# asam_mit_RFM.net
KiCad netlist of a schematic drawn in EAGLE
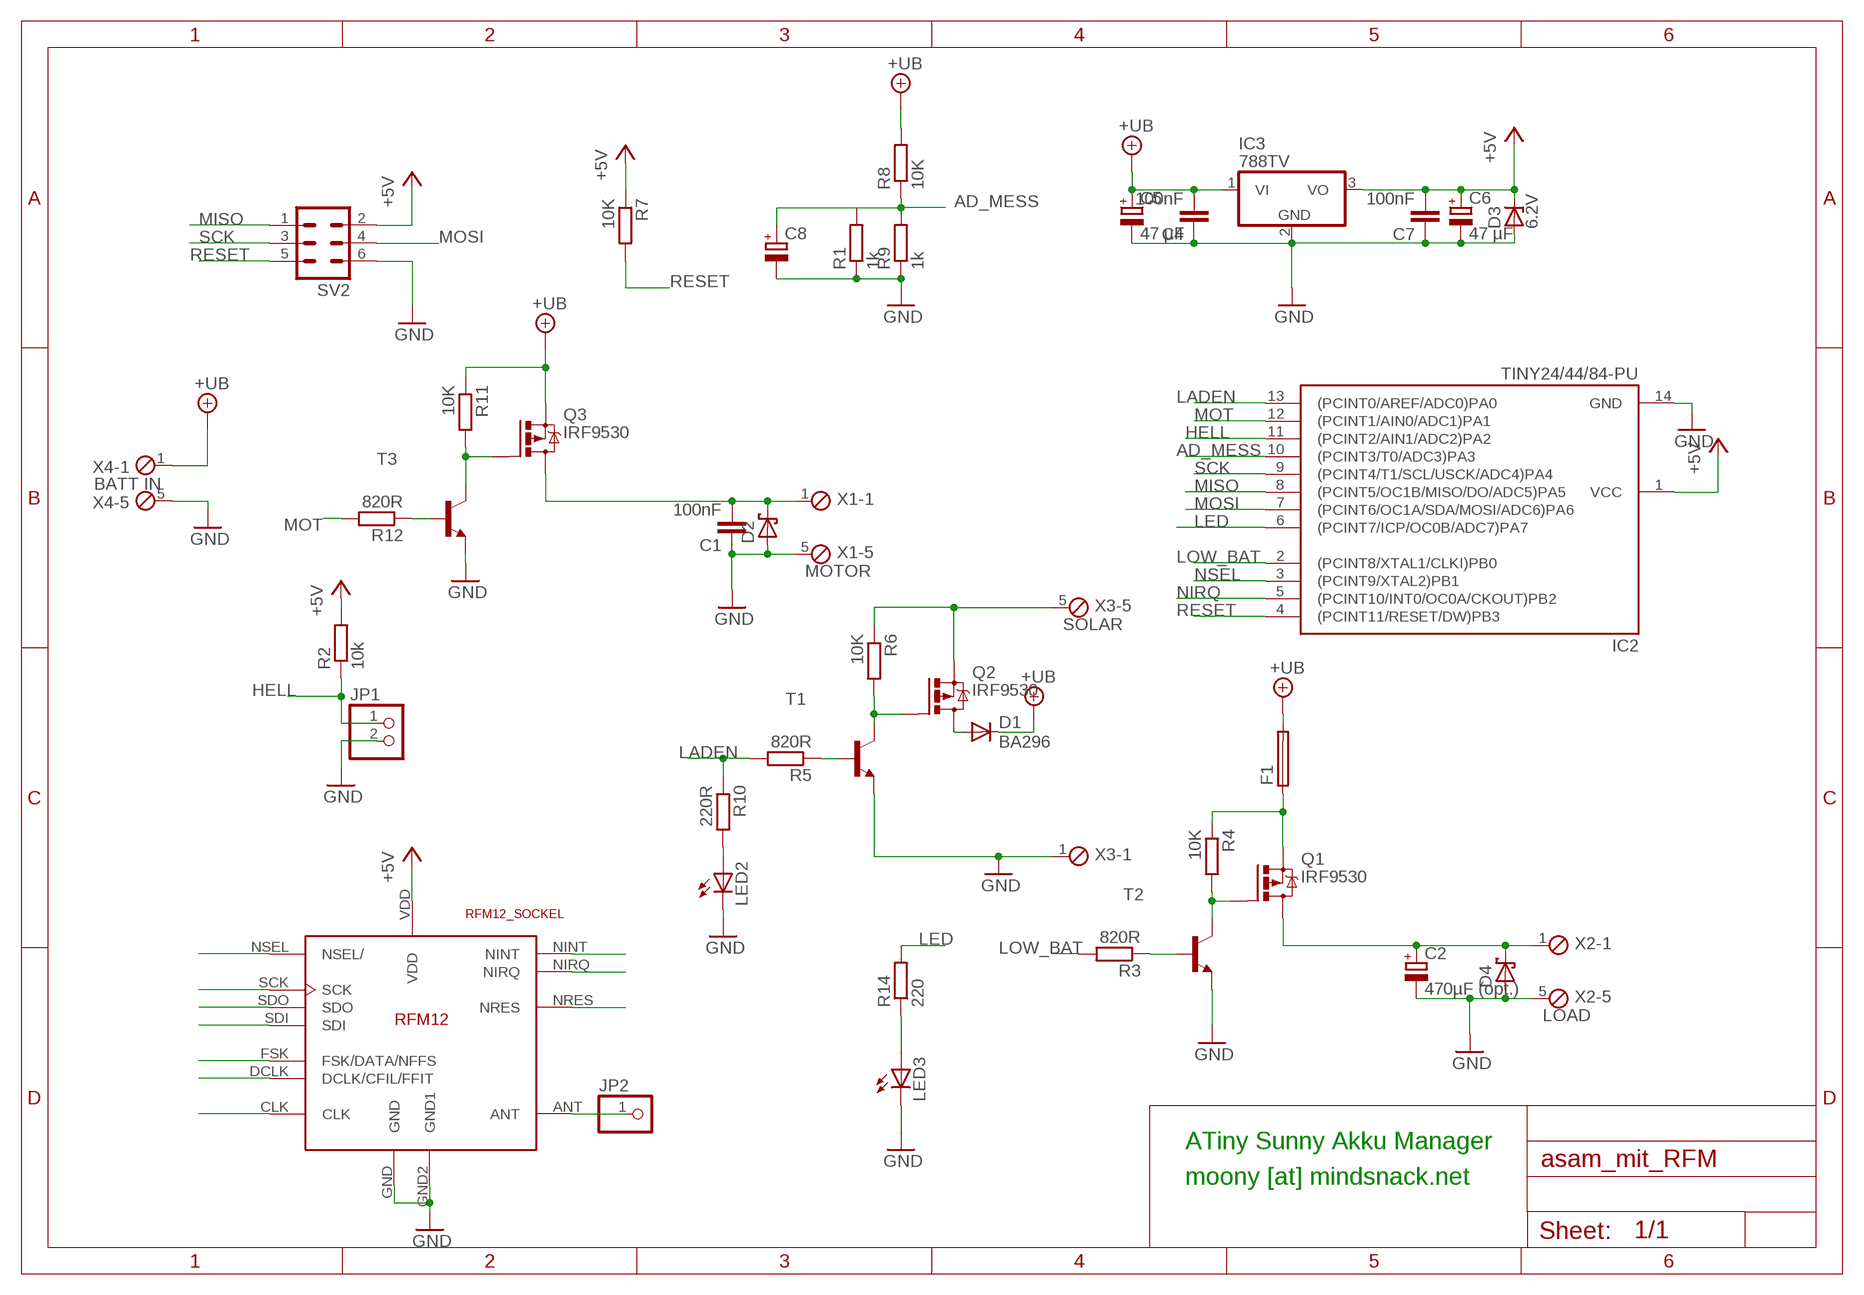
[diagram p0: schematic, sheet 1]

(export (version "E")
  (design (tool "Eeschema 10.0.6"))
  (components
    (comp (ref "C1")
      (value "100nF")
      (footprint "eagle-import:C075-032X103")
      (libsource (lib "eagle-import") (part "C-EU075-032X103"))
    )
    (comp (ref "C2")
      (value "470µF (opt.)")
      (footprint "eagle-import:E5-10,5")
      (libsource (lib "eagle-import") (part "CPOL-EUE5-10.5"))
    )
    (comp (ref "C4")
      (value "100nF")
      (footprint "eagle-import:C075-032X103")
      (libsource (lib "eagle-import") (part "C-EU075-032X103"))
    )
    (comp (ref "C5")
      (value "47 µF")
      (footprint "eagle-import:E5-10,5")
      (libsource (lib "eagle-import") (part "CPOL-EUE5-10.5"))
    )
    (comp (ref "C6")
      (value "47 µF")
      (footprint "eagle-import:E5-10,5")
      (libsource (lib "eagle-import") (part "CPOL-EUE5-10.5"))
    )
    (comp (ref "C7")
      (value "100nF")
      (footprint "eagle-import:C075-032X103")
      (libsource (lib "eagle-import") (part "C-EU075-032X103"))
    )
    (comp (ref "C8")
      (value "CPOL-EUE5-10.5")
      (footprint "eagle-import:E5-10,5")
      (libsource (lib "eagle-import") (part "CPOL-EUE5-10.5"))
    )
    (comp (ref "D1")
      (value "BA296")
      (footprint "eagle-import:P2-15")
      (libsource (lib "eagle-import") (part "BA296"))
    )
    (comp (ref "D2")
      (value "SCHOTTKY-DIODEDO35-7")
      (footprint "eagle-import:DO35-7")
      (libsource (lib "eagle-import") (part "SCHOTTKY-DIODEDO35-7"))
    )
    (comp (ref "D3")
      (value "6.2V")
      (footprint "eagle-import:C1702-15")
      (libsource (lib "eagle-import") (part "ZENER-DIODEC1702-15"))
    )
    (comp (ref "D4")
      (value "SCHOTTKY-DIODEDO35-7")
      (footprint "eagle-import:DO35-7")
      (libsource (lib "eagle-import") (part "SCHOTTKY-DIODEDO35-7"))
    )
    (comp (ref "F1")
      (value "SH22,5")
      (footprint "eagle-import:SH22,5")
      (fields (field (name "MF") "SCHURTER") (field (name "MPN") "0031.8201"))
      (libsource (lib "eagle-import") (part "SH22,5"))
    )
    (comp (ref "IC2")
      (value "TINY24/44/84-PU")
      (footprint "eagle-import:DIL14")
      (libsource (lib "eagle-import") (part "TINY24/44/84-PU"))
    )
    (comp (ref "IC3")
      (value "788TV")
      (footprint "eagle-import:TO220V")
      (libsource (lib "eagle-import") (part "78TV8"))
    )
    (comp (ref "JP1")
      (value "PINHD-1X2")
      (footprint "eagle-import:1X02")
      (libsource (lib "eagle-import") (part "PINHD-1X2"))
    )
    (comp (ref "JP2")
      (value "PINHD-1X1")
      (footprint "eagle-import:1X01")
      (libsource (lib "eagle-import") (part "PINHD-1X1"))
    )
    (comp (ref "LED2")
      (value "LED3MM")
      (footprint "eagle-import:LED3MM")
      (libsource (lib "eagle-import") (part "LED3MM"))
    )
    (comp (ref "LED3")
      (value "LED3MM")
      (footprint "eagle-import:LED3MM")
      (libsource (lib "eagle-import") (part "LED3MM"))
    )
    (comp (ref "Q1")
      (value "IRF9530")
      (footprint "eagle-import:TO220BV")
      (libsource (lib "eagle-import") (part "IRF9530"))
    )
    (comp (ref "Q2")
      (value "IRF9530")
      (footprint "eagle-import:TO220BV")
      (libsource (lib "eagle-import") (part "IRF9530"))
    )
    (comp (ref "Q3")
      (value "IRF9530")
      (footprint "eagle-import:TO220BV")
      (libsource (lib "eagle-import") (part "IRF9530"))
    )
    (comp (ref "R1")
      (value "1k")
      (footprint "eagle-import:0207_10")
      (libsource (lib "eagle-import") (part "R-EU_0207/10"))
    )
    (comp (ref "R2")
      (value "10k")
      (footprint "eagle-import:0207_10")
      (libsource (lib "eagle-import") (part "R-EU_0207/10"))
    )
    (comp (ref "R3")
      (value "820R")
      (footprint "eagle-import:0207_10")
      (libsource (lib "eagle-import") (part "R-EU_0207/10"))
    )
    (comp (ref "R4")
      (value "10K")
      (footprint "eagle-import:0207_12")
      (libsource (lib "eagle-import") (part "R-EU_0207/12"))
    )
    (comp (ref "R5")
      (value "820R")
      (footprint "eagle-import:0207_10")
      (libsource (lib "eagle-import") (part "R-EU_0207/10"))
    )
    (comp (ref "R6")
      (value "10K")
      (footprint "eagle-import:0207_12")
      (libsource (lib "eagle-import") (part "R-EU_0207/12"))
    )
    (comp (ref "R7")
      (value "10K")
      (footprint "eagle-import:0207_12")
      (libsource (lib "eagle-import") (part "R-EU_0207/12"))
    )
    (comp (ref "R8")
      (value "10K")
      (footprint "eagle-import:0207_10")
      (libsource (lib "eagle-import") (part "R-EU_0207/10"))
    )
    (comp (ref "R9")
      (value "1k")
      (footprint "eagle-import:0207_10")
      (libsource (lib "eagle-import") (part "R-EU_0207/10"))
    )
    (comp (ref "R10")
      (value "220R")
      (footprint "eagle-import:0207_10")
      (libsource (lib "eagle-import") (part "R-EU_0207/10"))
    )
    (comp (ref "R11")
      (value "10K")
      (footprint "eagle-import:0207_12")
      (libsource (lib "eagle-import") (part "R-EU_0207/12"))
    )
    (comp (ref "R12")
      (value "820R")
      (footprint "eagle-import:0207_10")
      (libsource (lib "eagle-import") (part "R-EU_0207/10"))
    )
    (comp (ref "R14")
      (value "220")
      (footprint "eagle-import:0207_10")
      (libsource (lib "eagle-import") (part "R-EU_0207/10"))
    )
    (comp (ref "SV2")
      (value "MA03-2")
      (footprint "eagle-import:MA03-2")
      (libsource (lib "eagle-import") (part "MA03-2"))
    )
    (comp (ref "T1")
      (value "BC546-NPN-TO92-CBE")
      (footprint "eagle-import:TO92-CBE")
      (libsource (lib "eagle-import") (part "-NPN-TO92-CBEBC546"))
    )
    (comp (ref "T2")
      (value "BC546-NPN-TO92-CBE")
      (footprint "eagle-import:TO92-CBE")
      (libsource (lib "eagle-import") (part "-NPN-TO92-CBEBC546"))
    )
    (comp (ref "T3")
      (value "BC546-NPN-TO92-CBE")
      (footprint "eagle-import:TO92-CBE")
      (libsource (lib "eagle-import") (part "-NPN-TO92-CBEBC546"))
    )
    (comp (ref "U$1")
      (value "RFM12_SOCKEL")
      (footprint "eagle-import:RFM12_SOCKEL")
      (libsource (lib "eagle-import") (part "RFM12_SOCKEL"))
    )
    (comp (ref "X1")
      (value "MOTOR")
      (footprint "eagle-import:5POL254")
      (libsource (lib "eagle-import") (part "MPT5"))
    )
    (comp (ref "X2")
      (value "LOAD")
      (footprint "eagle-import:5POL254")
      (libsource (lib "eagle-import") (part "MPT5"))
    )
    (comp (ref "X3")
      (value "SOLAR")
      (footprint "eagle-import:5POL254")
      (libsource (lib "eagle-import") (part "MPT5"))
    )
    (comp (ref "X4")
      (value "BATT IN")
      (footprint "eagle-import:5POL254")
      (libsource (lib "eagle-import") (part "MPT5"))
    )
  )
  (nets
    (net (code "1") (name "+5V") (class "Default")
      (node (ref "C6") (pin "+") (pinfunction "+_+") (pintype "passive"))
      (node (ref "C7") (pin "2") (pinfunction "2_2") (pintype "passive"))
      (node (ref "D3") (pin "C") (pinfunction "C_C") (pintype "passive"))
      (node (ref "IC2") (pin "1") (pinfunction "VCC_1") (pintype "power_in"))
      (node (ref "IC3") (pin "3") (pinfunction "VO_3") (pintype "passive"))
      (node (ref "R2") (pin "2") (pinfunction "2_2") (pintype "passive"))
      (node (ref "R7") (pin "1") (pinfunction "1_1") (pintype "passive"))
      (node (ref "SV2") (pin "2") (pinfunction "2_2") (pintype "passive"))
      (node (ref "U$1") (pin "VDD") (pinfunction "VDD_VDD") (pintype "power_in"))
    )
    (net (code "2") (name "+UB") (class "Default")
      (node (ref "C4") (pin "2") (pinfunction "2_2") (pintype "passive"))
      (node (ref "C5") (pin "+") (pinfunction "+_+") (pintype "passive"))
      (node (ref "D1") (pin "C") (pinfunction "C_C") (pintype "passive"))
      (node (ref "F1") (pin "2") (pinfunction "2_2") (pintype "passive"))
      (node (ref "IC3") (pin "1") (pinfunction "VI_1") (pintype "input"))
      (node (ref "Q3") (pin "S") (pinfunction "S_S") (pintype "passive"))
      (node (ref "R11") (pin "1") (pinfunction "1_1") (pintype "passive"))
      (node (ref "R8") (pin "2") (pinfunction "2_2") (pintype "passive"))
      (node (ref "X4") (pin "1") (pinfunction "1_1") (pintype "passive"))
    )
    (net (code "3") (name "/AD_MESS") (class "Default")
      (node (ref "C8") (pin "+") (pinfunction "+_+") (pintype "passive"))
      (node (ref "IC2") (pin "10") (pinfunction "(PCINT3/T0/ADC3)PA3_10") (pintype "bidirectional"))
      (node (ref "R1") (pin "2") (pinfunction "2_2") (pintype "passive"))
      (node (ref "R8") (pin "1") (pinfunction "1_1") (pintype "passive"))
      (node (ref "R9") (pin "2") (pinfunction "2_2") (pintype "passive"))
    )
    (net (code "4") (name "/HELL") (class "Default")
      (node (ref "IC2") (pin "11") (pinfunction "(PCINT2/AIN1/ADC2)PA2_11") (pintype "bidirectional"))
      (node (ref "JP1") (pin "1") (pinfunction "1_1") (pintype "passive"))
      (node (ref "R2") (pin "1") (pinfunction "1_1") (pintype "passive"))
    )
    (net (code "5") (name "/LADEN") (class "Default")
      (node (ref "IC2") (pin "13") (pinfunction "(PCINT0/AREF/ADC0)PA0_13") (pintype "bidirectional"))
      (node (ref "R10") (pin "1") (pinfunction "1_1") (pintype "passive"))
      (node (ref "R5") (pin "2") (pinfunction "2_2") (pintype "passive"))
    )
    (net (code "6") (name "/LED") (class "Default")
      (node (ref "IC2") (pin "6") (pinfunction "(PCINT7/ICP/OC0B/ADC7)PA7_6") (pintype "bidirectional"))
      (node (ref "R14") (pin "2") (pinfunction "2_2") (pintype "passive"))
    )
    (net (code "7") (name "/LOW_BAT") (class "Default")
      (node (ref "IC2") (pin "2") (pinfunction "(PCINT8/XTAL1/CLKI)PB0_2") (pintype "bidirectional"))
      (node (ref "R3") (pin "2") (pinfunction "2_2") (pintype "passive"))
    )
    (net (code "8") (name "/MISO") (class "Default")
      (node (ref "IC2") (pin "8") (pinfunction "(PCINT5/OC1B/MISO/DO/ADC5)PA5_8") (pintype "bidirectional"))
      (node (ref "SV2") (pin "1") (pinfunction "1_1") (pintype "passive"))
      (node (ref "U$1") (pin "SDI") (pinfunction "SDI_SDI") (pintype "input"))
    )
    (net (code "9") (name "/MOSI") (class "Default")
      (node (ref "IC2") (pin "7") (pinfunction "(PCINT6/OC1A/SDA/MOSI/ADC6)PA6_7") (pintype "bidirectional"))
      (node (ref "SV2") (pin "4") (pinfunction "4_4") (pintype "passive"))
      (node (ref "U$1") (pin "SDO") (pinfunction "SDO_SDO") (pintype "output"))
    )
    (net (code "10") (name "/MOT") (class "Default")
      (node (ref "IC2") (pin "12") (pinfunction "(PCINT1/AIN0/ADC1)PA1_12") (pintype "bidirectional"))
      (node (ref "R12") (pin "2") (pinfunction "2_2") (pintype "passive"))
    )
    (net (code "11") (name "/NIRQ") (class "Default")
      (node (ref "IC2") (pin "5") (pinfunction "(PCINT10/INT0/OC0A/CKOUT)PB2_5") (pintype "bidirectional"))
      (node (ref "U$1") (pin "NIRQ") (pinfunction "NIRQ_NIRQ") (pintype "output"))
    )
    (net (code "12") (name "/NSEL") (class "Default")
      (node (ref "IC2") (pin "3") (pinfunction "(PCINT9/XTAL2)PB1_3") (pintype "bidirectional"))
      (node (ref "U$1") (pin "NSEL") (pinfunction "NSEL/_NSEL") (pintype "input"))
    )
    (net (code "13") (name "/RESET") (class "Default")
      (node (ref "IC2") (pin "4") (pinfunction "(PCINT11/RESET/DW)PB3_4") (pintype "bidirectional"))
      (node (ref "R7") (pin "2") (pinfunction "2_2") (pintype "passive"))
      (node (ref "SV2") (pin "5") (pinfunction "5_5") (pintype "passive"))
    )
    (net (code "14") (name "/SCK") (class "Default")
      (node (ref "IC2") (pin "9") (pinfunction "(PCINT4/T1/SCL/USCK/ADC4)PA4_9") (pintype "bidirectional"))
      (node (ref "SV2") (pin "3") (pinfunction "3_3") (pintype "passive"))
      (node (ref "U$1") (pin "SCK") (pinfunction "SCK_SCK") (pintype "input"))
    )
    (net (code "15") (name "GND") (class "Default")
      (node (ref "C1") (pin "1") (pinfunction "1_1") (pintype "passive"))
      (node (ref "C2") (pin "-") (pinfunction "-_-") (pintype "passive"))
      (node (ref "C4") (pin "1") (pinfunction "1_1") (pintype "passive"))
      (node (ref "C5") (pin "-") (pinfunction "-_-") (pintype "passive"))
      (node (ref "C6") (pin "-") (pinfunction "-_-") (pintype "passive"))
      (node (ref "C7") (pin "1") (pinfunction "1_1") (pintype "passive"))
      (node (ref "C8") (pin "-") (pinfunction "-_-") (pintype "passive"))
      (node (ref "D2") (pin "A") (pinfunction "A_A") (pintype "passive"))
      (node (ref "D3") (pin "A") (pinfunction "A_A") (pintype "passive"))
      (node (ref "D4") (pin "A") (pinfunction "A_A") (pintype "passive"))
      (node (ref "IC2") (pin "14") (pinfunction "GND_14") (pintype "power_in"))
      (node (ref "IC3") (pin "2") (pinfunction "GND_2") (pintype "passive"))
      (node (ref "JP1") (pin "2") (pinfunction "2_2") (pintype "passive"))
      (node (ref "LED2") (pin "K") (pinfunction "C_K") (pintype "passive"))
      (node (ref "LED3") (pin "K") (pinfunction "C_K") (pintype "passive"))
      (node (ref "R1") (pin "1") (pinfunction "1_1") (pintype "passive"))
      (node (ref "R9") (pin "1") (pinfunction "1_1") (pintype "passive"))
      (node (ref "SV2") (pin "6") (pinfunction "6_6") (pintype "passive"))
      (node (ref "T1") (pin "E") (pinfunction "E_E") (pintype "passive"))
      (node (ref "T2") (pin "E") (pinfunction "E_E") (pintype "passive"))
      (node (ref "T3") (pin "E") (pinfunction "E_E") (pintype "passive"))
      (node (ref "U$1") (pin "GND") (pinfunction "GND_GND") (pintype "passive"))
      (node (ref "U$1") (pin "GND2") (pinfunction "GND1_GND2") (pintype "passive"))
      (node (ref "X1") (pin "5") (pinfunction "1_5") (pintype "passive"))
      (node (ref "X2") (pin "5") (pinfunction "1_5") (pintype "passive"))
      (node (ref "X3") (pin "1") (pinfunction "1_1") (pintype "passive"))
      (node (ref "X4") (pin "5") (pinfunction "1_5") (pintype "passive"))
    )
    (net (code "16") (name "Net-(C1-Pad2)") (class "Default")
      (node (ref "C1") (pin "2") (pinfunction "2_2") (pintype "passive"))
      (node (ref "D2") (pin "C") (pinfunction "C_C") (pintype "passive"))
      (node (ref "Q3") (pin "D") (pinfunction "D_D") (pintype "passive"))
      (node (ref "X1") (pin "1") (pinfunction "1_1") (pintype "passive"))
    )
    (net (code "17") (name "Net-(C2-Pad+)") (class "Default")
      (node (ref "C2") (pin "+") (pinfunction "+_+") (pintype "passive"))
      (node (ref "D4") (pin "C") (pinfunction "C_C") (pintype "passive"))
      (node (ref "Q1") (pin "D") (pinfunction "D_D") (pintype "passive"))
      (node (ref "X2") (pin "1") (pinfunction "1_1") (pintype "passive"))
    )
    (net (code "18") (name "Net-(D1-PadA)") (class "Default")
      (node (ref "D1") (pin "A") (pinfunction "A_A") (pintype "passive"))
      (node (ref "Q2") (pin "D") (pinfunction "D_D") (pintype "passive"))
    )
    (net (code "19") (name "Net-(F1-Pad1)") (class "Default")
      (node (ref "F1") (pin "1") (pinfunction "1_1") (pintype "passive"))
      (node (ref "Q1") (pin "S") (pinfunction "S_S") (pintype "passive"))
      (node (ref "R4") (pin "1") (pinfunction "1_1") (pintype "passive"))
    )
    (net (code "20") (name "Net-(JP2-Pad1)") (class "Default")
      (node (ref "JP2") (pin "1") (pinfunction "1_1") (pintype "passive"))
      (node (ref "U$1") (pin "ANT") (pinfunction "ANT_ANT") (pintype "bidirectional"))
    )
    (net (code "21") (name "Net-(LED2-PadA)") (class "Default")
      (node (ref "LED2") (pin "A") (pinfunction "A_A") (pintype "passive"))
      (node (ref "R10") (pin "2") (pinfunction "2_2") (pintype "passive"))
    )
    (net (code "22") (name "Net-(LED3-PadA)") (class "Default")
      (node (ref "LED3") (pin "A") (pinfunction "A_A") (pintype "passive"))
      (node (ref "R14") (pin "1") (pinfunction "1_1") (pintype "passive"))
    )
    (net (code "23") (name "Net-(Q1-PadG)") (class "Default")
      (node (ref "Q1") (pin "G") (pinfunction "G_G") (pintype "passive"))
      (node (ref "R4") (pin "2") (pinfunction "2_2") (pintype "passive"))
      (node (ref "T2") (pin "C") (pinfunction "C_C") (pintype "passive"))
    )
    (net (code "24") (name "Net-(Q2-PadG)") (class "Default")
      (node (ref "Q2") (pin "G") (pinfunction "G_G") (pintype "passive"))
      (node (ref "R6") (pin "2") (pinfunction "2_2") (pintype "passive"))
      (node (ref "T1") (pin "C") (pinfunction "C_C") (pintype "passive"))
    )
    (net (code "25") (name "Net-(Q3-PadG)") (class "Default")
      (node (ref "Q3") (pin "G") (pinfunction "G_G") (pintype "passive"))
      (node (ref "R11") (pin "2") (pinfunction "2_2") (pintype "passive"))
      (node (ref "T3") (pin "C") (pinfunction "C_C") (pintype "passive"))
    )
    (net (code "26") (name "Net-(R3-Pad1)") (class "Default")
      (node (ref "R3") (pin "1") (pinfunction "1_1") (pintype "passive"))
      (node (ref "T2") (pin "B") (pinfunction "B_B") (pintype "passive"))
    )
    (net (code "27") (name "Net-(R5-Pad1)") (class "Default")
      (node (ref "R5") (pin "1") (pinfunction "1_1") (pintype "passive"))
      (node (ref "T1") (pin "B") (pinfunction "B_B") (pintype "passive"))
    )
    (net (code "28") (name "Net-(R12-Pad1)") (class "Default")
      (node (ref "R12") (pin "1") (pinfunction "1_1") (pintype "passive"))
      (node (ref "T3") (pin "B") (pinfunction "B_B") (pintype "passive"))
    )
    (net (code "29") (name "Net-(X3E-1)") (class "Default")
      (node (ref "Q2") (pin "S") (pinfunction "S_S") (pintype "passive"))
      (node (ref "R6") (pin "1") (pinfunction "1_1") (pintype "passive"))
      (node (ref "X3") (pin "5") (pinfunction "1_5") (pintype "passive"))
    )
    (net (code "30") (name "unconnected-(U$1-DCLK{slash}CFIL{slash}FFIT-PadDCLK)") (class "Default")
      (node (ref "U$1") (pin "DCLK") (pinfunction "DCLK/CFIL/FFIT_DCLK") (pintype "bidirectional"))
    )
    (net (code "31") (name "unconnected-(U$1-FSK{slash}DATA{slash}NFFS-PadFSK)") (class "Default")
      (node (ref "U$1") (pin "FSK") (pinfunction "FSK/DATA/NFFS_FSK") (pintype "bidirectional"))
    )
    (net (code "32") (name "unconnected-(U$1-PadCLK)") (class "Default")
      (node (ref "U$1") (pin "CLK") (pinfunction "CLK_CLK") (pintype "output"))
    )
    (net (code "33") (name "unconnected-(U$1-PadNINT)") (class "Default")
      (node (ref "U$1") (pin "NINT") (pinfunction "NINT_NINT") (pintype "bidirectional"))
    )
    (net (code "34") (name "unconnected-(U$1-PadNRES)") (class "Default")
      (node (ref "U$1") (pin "NRES") (pinfunction "NRES_NRES") (pintype "bidirectional"))
    )
  )
)
